# Relay.net
KiCad netlist of a schematic drawn in Altium Designer
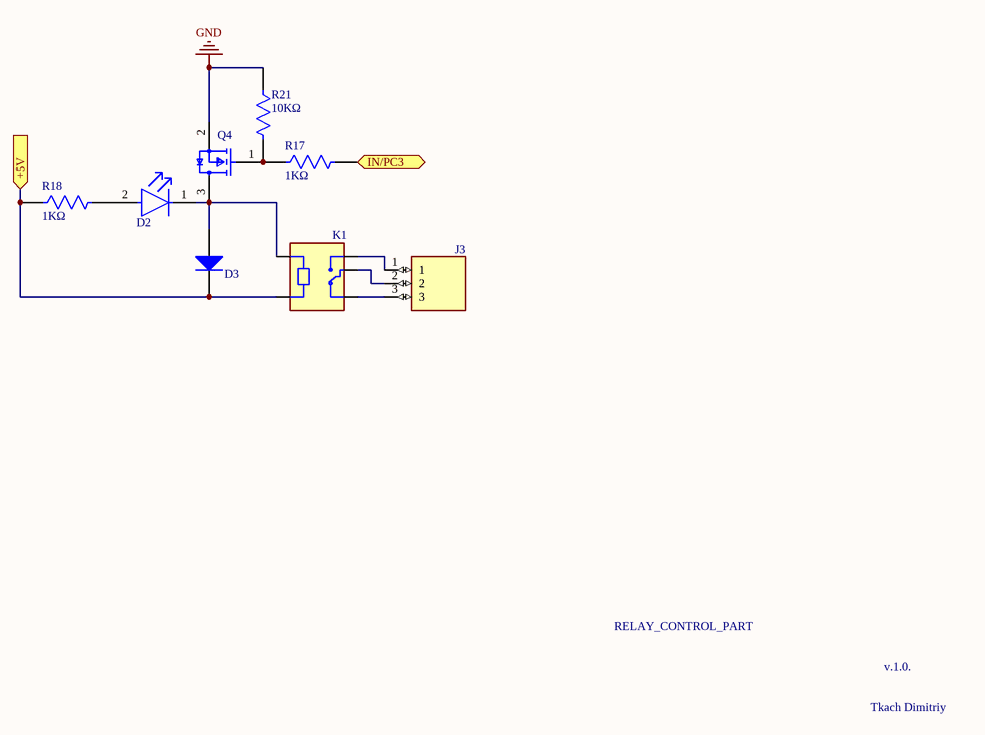
[diagram p0: Relay.SchDoc]

(export (version "E")
  (design (tool "Eeschema 10.0.6"))
  (components
    (comp (ref "D2")
      (value "LTST-C150KRKT")
      (footprint "FP-LTST-C150KRKT-MFG")
      (description "LED RED CLEAR 1206 SMD")
      (libsource (lib "Internal_Lib_Thermostat_STM8") (part "8706943c75ba83719d021d2fdc84c58"))
    )
    (comp (ref "D3")
      (value "1N4148W-7-F")
      (footprint "DIOD-SOD123-2_V")
      (description "Fast Switching Diode, 100 V, 0.15 A, -65 to 150 degC, 2-Pin?SOD123, RoHS, Tape and Reel")
      (fields (field (name "MANUFACTURER") "DiodesIncorporated"))
      (libsource (lib "Internal_Lib_Thermostat_STM8") (part "CMP-2000-04932-2"))
    )
    (comp (ref "J3")
      (value "39543-0603")
      (footprint "39543-0603")
      (description "3 Position Wire to Board Terminal Block Horizontal with Board 0.197 (5.00mm) Through Hole")
      (fields (field (name "MF") "Molex") (field (name "MP") "395430603"))
      (libsource (lib "Internal_Lib_Thermostat_STM8") (part "CMP-037-000000-1"))
    )
    (comp (ref "K1")
      (value "SRD-05VDC-SL-C")
      (footprint "RELAY_SRD-05VDC-SL-C")
      (fields (field (name "MF") "Songle Relay"))
      (libsource (lib "Internal_Lib_Thermostat_STM8") (part "CMP-013-000000-1"))
    )
    (comp (ref "Q4")
      (value "2N7002-7-F")
      (footprint "FP-SOT23-MFG")
      (description "MOSFET N-CH 60V 115MA SOT23-3")
      (fields (field (name "VOLTAGE") "60V"))
      (libsource (lib "Internal_Lib_Thermostat_STM8") (part "3b9c635fedb024a5347a57b145af9cc"))
    )
    (comp (ref "R17")
      (value "1KΩ")
      (footprint "RESC3216X06M")
      (description "CRGCQ1206 1KΩ 0.25W 1% ±100ppm/°C 200V")
      (fields
        (field (name "MANUFACTURER") "TE Connectivity")
        (field (name "MANUFACTURER PART NUMBER") "CRGCQ1206F1K0")
      )
      (libsource (lib "Internal_Lib_Thermostat_STM8") (part "CMP-03211-006592-1"))
    )
    (comp (ref "R18")
      (value "1KΩ")
      (footprint "RESC3216X06M")
      (description "CRGCQ1206 1KΩ 0.25W 1% ±100ppm/°C 200V")
      (fields
        (field (name "MANUFACTURER") "TE Connectivity")
        (field (name "MANUFACTURER PART NUMBER") "CRGCQ1206F1K0")
      )
      (libsource (lib "Internal_Lib_Thermostat_STM8") (part "CMP-03211-006592-1"))
    )
    (comp (ref "R21")
      (value "CRGP1206F10K")
      (footprint "RESC3216X06M")
      (description "CRGP 1206 10K 1%")
      (fields
        (field (name "OCTOPART") "https://octopart.com/crgp1206f10k-te+connectivity-91018843")
        (field (name "TOLERANCE") "0.01")
        (field (name "RESISTANCE") "10KΩ")
      )
      (libsource (lib "Internal_Lib_Thermostat_STM8") (part "CMP-03211-004788-1"))
    )
  )
  (nets
    (net (code "1") (name "/+5V") (class "Default")
      (node (ref "D3") (pin "2") (pinfunction "K_2") (pintype "passive"))
      (node (ref "K1") (pin "A2") (pinfunction "A2_A2") (pintype "passive"))
      (node (ref "R18") (pin "1") (pinfunction "1_1") (pintype "passive"))
    )
    (net (code "2") (name "/IN{slash}PC3") (class "Default")
      (node (ref "R17") (pin "2") (pinfunction "2_2") (pintype "passive"))
    )
    (net (code "3") (name "GND") (class "Default")
      (node (ref "Q4") (pin "2") (pinfunction "S_2") (pintype "passive"))
      (node (ref "R21") (pin "1") (pinfunction "1_1") (pintype "passive"))
    )
    (net (code "4") (name "Net-(D2-A)") (class "Default")
      (node (ref "D2") (pin "2") (pinfunction "A_2") (pintype "passive"))
      (node (ref "R18") (pin "2") (pinfunction "2_2") (pintype "passive"))
    )
    (net (code "5") (name "Net-(D2-C)") (class "Default")
      (node (ref "D2") (pin "1") (pinfunction "C_1") (pintype "passive"))
      (node (ref "D3") (pin "1") (pinfunction "A_1") (pintype "passive"))
      (node (ref "K1") (pin "A1") (pinfunction "A1_A1") (pintype "passive"))
      (node (ref "Q4") (pin "3") (pinfunction "D_3") (pintype "passive"))
    )
    (net (code "6") (name "Net-(J3-Pad1)") (class "Default")
      (node (ref "J3") (pin "1") (pinfunction "1_1") (pintype "bidirectional"))
      (node (ref "K1") (pin "NO") (pinfunction "NO_NO") (pintype "passive"))
    )
    (net (code "7") (name "Net-(J3-Pad2)") (class "Default")
      (node (ref "J3") (pin "2") (pinfunction "2_2") (pintype "bidirectional"))
      (node (ref "K1") (pin "COM") (pinfunction "COM_COM") (pintype "passive"))
    )
    (net (code "8") (name "Net-(J3-Pad3)") (class "Default")
      (node (ref "J3") (pin "3") (pinfunction "3_3") (pintype "bidirectional"))
      (node (ref "K1") (pin "NC") (pinfunction "NC_NC") (pintype "passive"))
    )
    (net (code "9") (name "Net-(Q4-G)") (class "Default")
      (node (ref "Q4") (pin "1") (pinfunction "G_1") (pintype "passive"))
      (node (ref "R17") (pin "1") (pinfunction "1_1") (pintype "passive"))
      (node (ref "R21") (pin "2") (pinfunction "2_2") (pintype "passive"))
    )
  )
)
